# board1.net
KiCad netlist of a schematic drawn in EAGLE
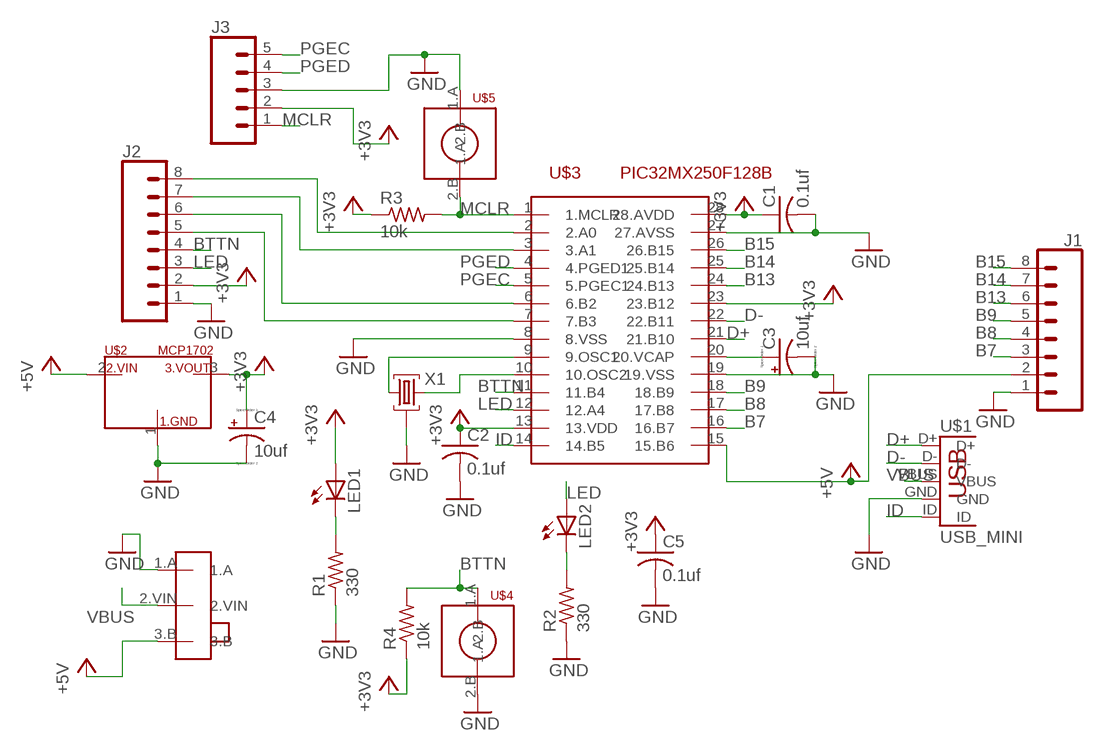
[diagram p0: schematic, sheet 1]

(export (version "E")
  (design (tool "Eeschema 10.0.6"))
  (components
    (comp (ref "C1")
      (value "0.1uf")
      (footprint "eagle-import:C025-025X050")
      (libsource (lib "eagle-import") (part "C-US025-025X050"))
    )
    (comp (ref "C2")
      (value "0.1uf")
      (footprint "eagle-import:C025-025X050")
      (libsource (lib "eagle-import") (part "C-US025-025X050"))
    )
    (comp (ref "C3")
      (value "10uf")
      (footprint "eagle-import:E2,5-6E")
      (libsource (lib "eagle-import") (part "CPOL-USE2,5-6E"))
    )
    (comp (ref "C4")
      (value "10uf")
      (footprint "eagle-import:E2,5-6E")
      (libsource (lib "eagle-import") (part "CPOL-USE2,5-6E"))
    )
    (comp (ref "C5")
      (value "0.1uf")
      (footprint "eagle-import:C025-025X050")
      (libsource (lib "eagle-import") (part "C-US025-025X050"))
    )
    (comp (ref "J1")
      (value "CONN_08\"")
      (footprint "eagle-import:1X08")
      (libsource (lib "eagle-import") (part "CONN_08{dblquote}"))
    )
    (comp (ref "J2")
      (value "CONN_08\"")
      (footprint "eagle-import:1X08")
      (libsource (lib "eagle-import") (part "CONN_08{dblquote}"))
    )
    (comp (ref "J3")
      (value "CONN_05")
      (footprint "eagle-import:1X05")
      (libsource (lib "eagle-import") (part "CONN_05"))
    )
    (comp (ref "LED1")
      (value "LED5MM")
      (footprint "eagle-import:LED5MM")
      (libsource (lib "eagle-import") (part "LED5MM"))
    )
    (comp (ref "LED2")
      (value "LED5MM")
      (footprint "eagle-import:LED5MM")
      (libsource (lib "eagle-import") (part "LED5MM"))
    )
    (comp (ref "R1")
      (value "330")
      (footprint "eagle-import:0204_5")
      (libsource (lib "eagle-import") (part "R-US_0204/5"))
    )
    (comp (ref "R2")
      (value "330")
      (footprint "eagle-import:0204_5")
      (libsource (lib "eagle-import") (part "R-US_0204/5"))
    )
    (comp (ref "R3")
      (value "10k")
      (footprint "eagle-import:0204_5")
      (libsource (lib "eagle-import") (part "R-US_0204/5"))
    )
    (comp (ref "R4")
      (value "10k")
      (footprint "eagle-import:0204_5")
      (libsource (lib "eagle-import") (part "R-US_0204/5"))
    )
    (comp (ref "U$1")
      (value "USB_MINI")
      (footprint "eagle-import:USB-MB-H")
      (libsource (lib "eagle-import") (part "USB_MINI"))
    )
    (comp (ref "U$2")
      (value "MCP1702")
      (footprint "eagle-import:TO92")
      (libsource (lib "eagle-import") (part "MCP1702"))
    )
    (comp (ref "U$3")
      (value "PIC32MX250F128B")
      (footprint "eagle-import:DIL28-3")
      (libsource (lib "eagle-import") (part "PIC32MX250F128B"))
    )
    (comp (ref "U$4")
      (value "PUSH_BUTTON")
      (footprint "eagle-import:PUSH_BUTTON")
      (libsource (lib "eagle-import") (part "PUSH_BUTTON"))
    )
    (comp (ref "U$5")
      (value "PUSH_BUTTON")
      (footprint "eagle-import:PUSH_BUTTON")
      (libsource (lib "eagle-import") (part "PUSH_BUTTON"))
    )
    (comp (ref "U$6")
      (value "SLIDE_SWITCH")
      (footprint "eagle-import:SLIDE_SWITCH")
      (libsource (lib "eagle-import") (part "SLIDE_SWITCH"))
    )
    (comp (ref "X1")
      (value "HC49-HC49-3L")
      (footprint "eagle-import:HC49-3L")
      (libsource (lib "eagle-import") (part "HC49-HC49-3L"))
    )
  )
  (nets
    (net (code "1") (name "+3V3") (class "Default")
      (node (ref "C1") (pin "1") (pinfunction "1_1") (pintype "passive"))
      (node (ref "C2") (pin "1") (pinfunction "1_1") (pintype "passive"))
      (node (ref "C4") (pin "+") (pinfunction "+_+") (pintype "passive"))
      (node (ref "C5") (pin "1") (pinfunction "1_1") (pintype "passive"))
      (node (ref "J2") (pin "2") (pinfunction "2_2") (pintype "passive"))
      (node (ref "J3") (pin "2") (pinfunction "2_2") (pintype "passive"))
      (node (ref "LED1") (pin "A") (pinfunction "A_A") (pintype "passive"))
      (node (ref "R3") (pin "1") (pinfunction "1_1") (pintype "passive"))
      (node (ref "R4") (pin "1") (pinfunction "1_1") (pintype "passive"))
      (node (ref "U$2") (pin "3") (pinfunction "3.VOUT_3") (pintype "bidirectional"))
      (node (ref "U$3") (pin "13") (pinfunction "13.VDD_13") (pintype "bidirectional"))
      (node (ref "U$3") (pin "23") (pinfunction "23.B12_23") (pintype "bidirectional"))
      (node (ref "U$3") (pin "28") (pinfunction "28.AVDD_28") (pintype "bidirectional"))
    )
    (net (code "2") (name "+5V") (class "Default")
      (node (ref "J1") (pin "2") (pinfunction "2_2") (pintype "passive"))
      (node (ref "U$2") (pin "2") (pinfunction "2.VIN_2") (pintype "bidirectional"))
      (node (ref "U$3") (pin "15") (pinfunction "15.B6_15") (pintype "bidirectional"))
      (node (ref "U$6") (pin "3.B") (pinfunction "3.B_3.B") (pintype "bidirectional"))
    )
    (net (code "3") (name "/B7") (class "Default")
      (node (ref "J1") (pin "3") (pinfunction "3_3") (pintype "passive"))
      (node (ref "U$3") (pin "16") (pinfunction "16.B7_16") (pintype "bidirectional"))
    )
    (net (code "4") (name "/B8") (class "Default")
      (node (ref "J1") (pin "4") (pinfunction "4_4") (pintype "passive"))
      (node (ref "U$3") (pin "17") (pinfunction "17.B8_17") (pintype "bidirectional"))
    )
    (net (code "5") (name "/B9") (class "Default")
      (node (ref "J1") (pin "5") (pinfunction "5_5") (pintype "passive"))
      (node (ref "U$3") (pin "18") (pinfunction "18.B9_18") (pintype "bidirectional"))
    )
    (net (code "6") (name "/B13") (class "Default")
      (node (ref "J1") (pin "6") (pinfunction "6_6") (pintype "passive"))
      (node (ref "U$3") (pin "24") (pinfunction "24.B13_24") (pintype "bidirectional"))
    )
    (net (code "7") (name "/B14") (class "Default")
      (node (ref "J1") (pin "7") (pinfunction "7_7") (pintype "passive"))
      (node (ref "U$3") (pin "25") (pinfunction "25.B14_25") (pintype "bidirectional"))
    )
    (net (code "8") (name "/B15") (class "Default")
      (node (ref "J1") (pin "8") (pinfunction "8_8") (pintype "passive"))
      (node (ref "U$3") (pin "26") (pinfunction "26.B15_26") (pintype "bidirectional"))
    )
    (net (code "9") (name "/BTTN") (class "Default")
      (node (ref "J2") (pin "4") (pinfunction "4_4") (pintype "passive"))
      (node (ref "R4") (pin "2") (pinfunction "2_2") (pintype "passive"))
      (node (ref "U$3") (pin "11") (pinfunction "11.B4_11") (pintype "bidirectional"))
      (node (ref "U$4") (pin "1.A") (pinfunction "1.A_1.A") (pintype "bidirectional"))
    )
    (net (code "10") (name "/D+") (class "Default")
      (node (ref "U$1") (pin "D+") (pinfunction "D+_D+") (pintype "bidirectional"))
      (node (ref "U$3") (pin "21") (pinfunction "21.B10_21") (pintype "bidirectional"))
    )
    (net (code "11") (name "/D-") (class "Default")
      (node (ref "U$1") (pin "D-") (pinfunction "D-_D-") (pintype "bidirectional"))
      (node (ref "U$3") (pin "22") (pinfunction "22.B11_22") (pintype "bidirectional"))
    )
    (net (code "12") (name "/ID") (class "Default")
      (node (ref "U$1") (pin "ID") (pinfunction "ID_ID") (pintype "bidirectional"))
      (node (ref "U$3") (pin "14") (pinfunction "14.B5_14") (pintype "bidirectional"))
    )
    (net (code "13") (name "/LED") (class "Default")
      (node (ref "J2") (pin "3") (pinfunction "3_3") (pintype "passive"))
      (node (ref "LED2") (pin "A") (pinfunction "A_A") (pintype "passive"))
      (node (ref "U$3") (pin "12") (pinfunction "12.A4_12") (pintype "bidirectional"))
    )
    (net (code "14") (name "/MCLR") (class "Default")
      (node (ref "J3") (pin "1") (pinfunction "1_1") (pintype "passive"))
      (node (ref "R3") (pin "2") (pinfunction "2_2") (pintype "passive"))
      (node (ref "U$3") (pin "1") (pinfunction "1.MCLR_1") (pintype "bidirectional"))
      (node (ref "U$5") (pin "2.B") (pinfunction "2.B_2.B") (pintype "bidirectional"))
    )
    (net (code "15") (name "/PGEC") (class "Default")
      (node (ref "J3") (pin "5") (pinfunction "5_5") (pintype "passive"))
      (node (ref "U$3") (pin "5") (pinfunction "5.PGEC1_5") (pintype "bidirectional"))
    )
    (net (code "16") (name "/PGED") (class "Default")
      (node (ref "J3") (pin "4") (pinfunction "4_4") (pintype "passive"))
      (node (ref "U$3") (pin "4") (pinfunction "4.PGED1_4") (pintype "bidirectional"))
    )
    (net (code "17") (name "/VBUS") (class "Default")
      (node (ref "U$1") (pin "VBUS") (pinfunction "VBUS_VBUS") (pintype "bidirectional"))
      (node (ref "U$6") (pin "2.VIN") (pinfunction "2.VIN_2.VIN") (pintype "bidirectional"))
    )
    (net (code "18") (name "GND") (class "Default")
      (node (ref "C1") (pin "2") (pinfunction "2_2") (pintype "passive"))
      (node (ref "C2") (pin "2") (pinfunction "2_2") (pintype "passive"))
      (node (ref "C3") (pin "-") (pinfunction "-_-") (pintype "passive"))
      (node (ref "C4") (pin "-") (pinfunction "-_-") (pintype "passive"))
      (node (ref "C5") (pin "2") (pinfunction "2_2") (pintype "passive"))
      (node (ref "J1") (pin "1") (pinfunction "1_1") (pintype "passive"))
      (node (ref "J2") (pin "1") (pinfunction "1_1") (pintype "passive"))
      (node (ref "J3") (pin "3") (pinfunction "3_3") (pintype "passive"))
      (node (ref "R1") (pin "1") (pinfunction "1_1") (pintype "passive"))
      (node (ref "R2") (pin "1") (pinfunction "1_1") (pintype "passive"))
      (node (ref "U$1") (pin "GND") (pinfunction "GND_GND") (pintype "bidirectional"))
      (node (ref "U$2") (pin "1") (pinfunction "1.GND_1") (pintype "bidirectional"))
      (node (ref "U$3") (pin "19") (pinfunction "19.VSS_19") (pintype "bidirectional"))
      (node (ref "U$3") (pin "27") (pinfunction "27.AVSS_27") (pintype "bidirectional"))
      (node (ref "U$3") (pin "8") (pinfunction "8.VSS_8") (pintype "bidirectional"))
      (node (ref "U$4") (pin "2.B") (pinfunction "2.B_2.B") (pintype "bidirectional"))
      (node (ref "U$5") (pin "1.A") (pinfunction "1.A_1.A") (pintype "bidirectional"))
      (node (ref "U$6") (pin "1.A") (pinfunction "1.A_1.A") (pintype "bidirectional"))
      (node (ref "X1") (pin "2") (pinfunction "2_2") (pintype "passive"))
    )
    (net (code "19") (name "Net-(LED1-C)") (class "Default")
      (node (ref "LED1") (pin "K") (pinfunction "C_K") (pintype "passive"))
      (node (ref "R1") (pin "2") (pinfunction "2_2") (pintype "passive"))
    )
    (net (code "20") (name "Net-(LED2-C)") (class "Default")
      (node (ref "LED2") (pin "K") (pinfunction "C_K") (pintype "passive"))
      (node (ref "R2") (pin "2") (pinfunction "2_2") (pintype "passive"))
    )
    (net (code "21") (name "Net-(U$3-2.A0)") (class "Default")
      (node (ref "J2") (pin "8") (pinfunction "8_8") (pintype "passive"))
      (node (ref "U$3") (pin "2") (pinfunction "2.A0_2") (pintype "bidirectional"))
    )
    (net (code "22") (name "Net-(U$3-3.A1)") (class "Default")
      (node (ref "J2") (pin "7") (pinfunction "7_7") (pintype "passive"))
      (node (ref "U$3") (pin "3") (pinfunction "3.A1_3") (pintype "bidirectional"))
    )
    (net (code "23") (name "Net-(U$3-6.B2)") (class "Default")
      (node (ref "J2") (pin "6") (pinfunction "6_6") (pintype "passive"))
      (node (ref "U$3") (pin "6") (pinfunction "6.B2_6") (pintype "bidirectional"))
    )
    (net (code "24") (name "Net-(U$3-7.B3)") (class "Default")
      (node (ref "J2") (pin "5") (pinfunction "5_5") (pintype "passive"))
      (node (ref "U$3") (pin "7") (pinfunction "7.B3_7") (pintype "bidirectional"))
    )
    (net (code "25") (name "Net-(U$3-9.OSC1)") (class "Default")
      (node (ref "U$3") (pin "9") (pinfunction "9.OSC1_9") (pintype "bidirectional"))
      (node (ref "X1") (pin "1") (pinfunction "1_1") (pintype "passive"))
    )
    (net (code "26") (name "Net-(U$3-10.OSC2)") (class "Default")
      (node (ref "U$3") (pin "10") (pinfunction "10.OSC2_10") (pintype "bidirectional"))
      (node (ref "X1") (pin "3") (pinfunction "3_3") (pintype "passive"))
    )
    (net (code "27") (name "Net-(U$3-20.VCAP)") (class "Default")
      (node (ref "C3") (pin "+") (pinfunction "+_+") (pintype "passive"))
      (node (ref "U$3") (pin "20") (pinfunction "20.VCAP_20") (pintype "bidirectional"))
    )
  )
)
